# AD8403_SVF.net
KiCad netlist of a schematic drawn in EAGLE
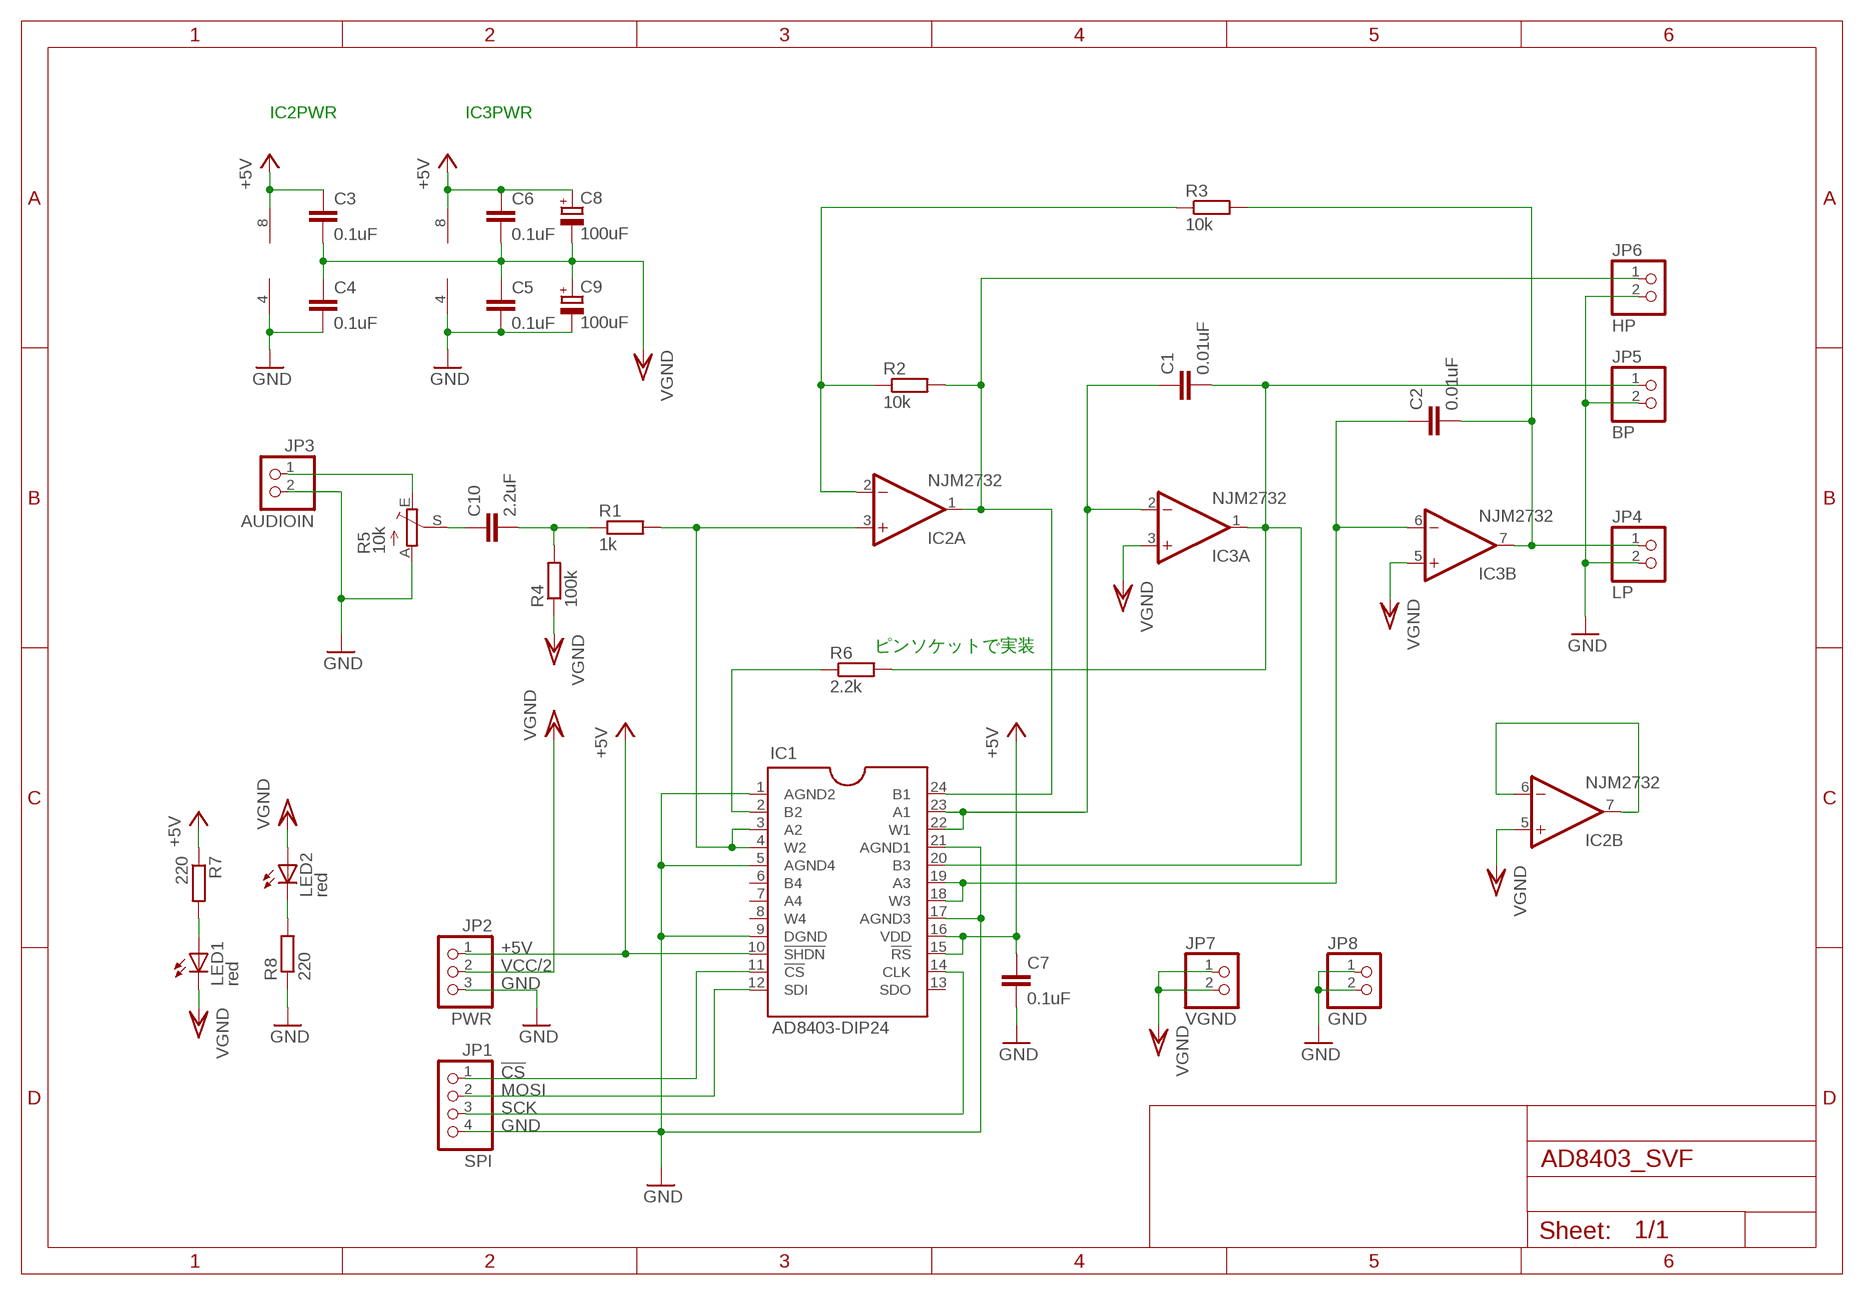
[diagram p0: schematic, sheet 1]

(export (version "E")
  (design (tool "Eeschema 10.0.6"))
  (components
    (comp (ref "C1")
      (value "0.01uF")
      (footprint "eagle-import:C050-025X075")
      (libsource (lib "eagle-import") (part "C-EU050-025X075"))
    )
    (comp (ref "C2")
      (value "0.01uF")
      (footprint "eagle-import:C050-025X075")
      (libsource (lib "eagle-import") (part "C-EU050-025X075"))
    )
    (comp (ref "C3")
      (value "0.1uF")
      (footprint "eagle-import:C025-024X044")
      (libsource (lib "eagle-import") (part "C-EU025-024X044"))
    )
    (comp (ref "C4")
      (value "0.1uF")
      (footprint "eagle-import:C025-024X044")
      (libsource (lib "eagle-import") (part "C-EU025-024X044"))
    )
    (comp (ref "C5")
      (value "0.1uF")
      (footprint "eagle-import:C025-024X044")
      (libsource (lib "eagle-import") (part "C-EU025-024X044"))
    )
    (comp (ref "C6")
      (value "0.1uF")
      (footprint "eagle-import:C025-024X044")
      (libsource (lib "eagle-import") (part "C-EU025-024X044"))
    )
    (comp (ref "C7")
      (value "0.1uF")
      (footprint "eagle-import:C025-024X044")
      (libsource (lib "eagle-import") (part "C-EU025-024X044"))
    )
    (comp (ref "C8")
      (value "100uF")
      (footprint "eagle-import:E2,5-7")
      (libsource (lib "eagle-import") (part "CPOL-EUE2.5-7"))
    )
    (comp (ref "C9")
      (value "100uF")
      (footprint "eagle-import:E2,5-7")
      (libsource (lib "eagle-import") (part "CPOL-EUE2.5-7"))
    )
    (comp (ref "C10")
      (value "2.2uF")
      (footprint "eagle-import:C050-055X075")
      (libsource (lib "eagle-import") (part "C-EU050-055X075"))
    )
    (comp (ref "IC1")
      (value "AD8403-DIP24")
      (footprint "eagle-import:AD8403_DIP24")
      (libsource (lib "eagle-import") (part "AD8403-DIP24"))
    )
    (comp (ref "IC2")
      (value "NJM2732")
      (footprint "eagle-import:DIL08")
      (libsource (lib "eagle-import") (part "4558NLM"))
    )
    (comp (ref "IC3")
      (value "NJM2732")
      (footprint "eagle-import:DIL08")
      (libsource (lib "eagle-import") (part "4558NLM"))
    )
    (comp (ref "JP1")
      (value "SPI")
      (footprint "eagle-import:1X04")
      (libsource (lib "eagle-import") (part "PINHD-1X4"))
    )
    (comp (ref "JP2")
      (value "PWR")
      (footprint "eagle-import:1X03")
      (libsource (lib "eagle-import") (part "PINHD-1X3"))
    )
    (comp (ref "JP3")
      (value "AUDIOIN")
      (footprint "eagle-import:1X02")
      (libsource (lib "eagle-import") (part "PINHD-1X2"))
    )
    (comp (ref "JP4")
      (value "LP")
      (footprint "eagle-import:1X02")
      (libsource (lib "eagle-import") (part "PINHD-1X2"))
    )
    (comp (ref "JP5")
      (value "BP")
      (footprint "eagle-import:1X02")
      (libsource (lib "eagle-import") (part "PINHD-1X2"))
    )
    (comp (ref "JP6")
      (value "HP")
      (footprint "eagle-import:1X02")
      (libsource (lib "eagle-import") (part "PINHD-1X2"))
    )
    (comp (ref "JP7")
      (value "VGND")
      (footprint "eagle-import:1X02")
      (libsource (lib "eagle-import") (part "PINHD-1X2"))
    )
    (comp (ref "JP8")
      (value "GND")
      (footprint "eagle-import:1X02")
      (libsource (lib "eagle-import") (part "PINHD-1X2"))
    )
    (comp (ref "LED1")
      (value "red")
      (footprint "eagle-import:LED3MM")
      (libsource (lib "eagle-import") (part "LED3MM"))
    )
    (comp (ref "LED2")
      (value "red")
      (footprint "eagle-import:LED3MM")
      (libsource (lib "eagle-import") (part "LED3MM"))
    )
    (comp (ref "R1")
      (value "1k")
      (footprint "eagle-import:0207_7")
      (libsource (lib "eagle-import") (part "R-EU_0207/7"))
    )
    (comp (ref "R2")
      (value "10k")
      (footprint "eagle-import:0207_7")
      (libsource (lib "eagle-import") (part "R-EU_0207/7"))
    )
    (comp (ref "R3")
      (value "10k")
      (footprint "eagle-import:0207_7")
      (libsource (lib "eagle-import") (part "R-EU_0207/7"))
    )
    (comp (ref "R4")
      (value "100k")
      (footprint "eagle-import:0207_7")
      (libsource (lib "eagle-import") (part "R-EU_0207/7"))
    )
    (comp (ref "R5")
      (value "10k")
      (footprint "eagle-import:B25P")
      (libsource (lib "eagle-import") (part "TRIM_EU-B25P"))
    )
    (comp (ref "R6")
      (value "2.2k")
      (footprint "eagle-import:0207_7")
      (libsource (lib "eagle-import") (part "R-EU_0207/7"))
    )
    (comp (ref "R7")
      (value "220")
      (footprint "eagle-import:0204V")
      (libsource (lib "eagle-import") (part "R-EU_0204/2V"))
    )
    (comp (ref "R8")
      (value "220")
      (footprint "eagle-import:0204V")
      (libsource (lib "eagle-import") (part "R-EU_0204/2V"))
    )
  )
  (nets
    (net (code "1") (name "+5V") (class "Default")
      (node (ref "C3") (pin "1") (pinfunction "1_1") (pintype "passive"))
      (node (ref "C6") (pin "1") (pinfunction "1_1") (pintype "passive"))
      (node (ref "C7") (pin "1") (pinfunction "1_1") (pintype "passive"))
      (node (ref "C8") (pin "+") (pinfunction "+_+") (pintype "passive"))
      (node (ref "IC1") (pin "10") (pinfunction "~{SHDN}_10") (pintype "passive"))
      (node (ref "IC1") (pin "15") (pinfunction "~{RS}_15") (pintype "passive"))
      (node (ref "IC1") (pin "16") (pinfunction "VDD_16") (pintype "passive"))
      (node (ref "IC2") (pin "8") (pinfunction "V+_8") (pintype "power_in"))
      (node (ref "IC3") (pin "8") (pinfunction "V+_8") (pintype "power_in"))
      (node (ref "JP2") (pin "1") (pinfunction "1_1") (pintype "passive"))
      (node (ref "R7") (pin "1") (pinfunction "1_1") (pintype "passive"))
    )
    (net (code "2") (name "/MOSI") (class "Default")
      (node (ref "IC1") (pin "12") (pinfunction "SDI_12") (pintype "passive"))
      (node (ref "JP1") (pin "2") (pinfunction "2_2") (pintype "passive"))
    )
    (net (code "3") (name "/SCK") (class "Default")
      (node (ref "IC1") (pin "14") (pinfunction "CLK_14") (pintype "passive"))
      (node (ref "JP1") (pin "3") (pinfunction "3_3") (pintype "passive"))
    )
    (net (code "4") (name "/~{CS}") (class "Default")
      (node (ref "IC1") (pin "11") (pinfunction "~{CS}_11") (pintype "passive"))
      (node (ref "JP1") (pin "1") (pinfunction "1_1") (pintype "passive"))
    )
    (net (code "5") (name "GND") (class "Default")
      (node (ref "C4") (pin "2") (pinfunction "2_2") (pintype "passive"))
      (node (ref "C5") (pin "2") (pinfunction "2_2") (pintype "passive"))
      (node (ref "C7") (pin "2") (pinfunction "2_2") (pintype "passive"))
      (node (ref "C9") (pin "-") (pinfunction "-_-") (pintype "passive"))
      (node (ref "IC1") (pin "1") (pinfunction "AGND2_1") (pintype "passive"))
      (node (ref "IC1") (pin "17") (pinfunction "AGND3_17") (pintype "passive"))
      (node (ref "IC1") (pin "21") (pinfunction "AGND1_21") (pintype "passive"))
      (node (ref "IC1") (pin "5") (pinfunction "AGND4_5") (pintype "passive"))
      (node (ref "IC1") (pin "9") (pinfunction "DGND_9") (pintype "passive"))
      (node (ref "IC2") (pin "4") (pinfunction "V-_4") (pintype "power_in"))
      (node (ref "IC3") (pin "4") (pinfunction "V-_4") (pintype "power_in"))
      (node (ref "JP1") (pin "4") (pinfunction "4_4") (pintype "passive"))
      (node (ref "JP2") (pin "3") (pinfunction "3_3") (pintype "passive"))
      (node (ref "JP3") (pin "2") (pinfunction "2_2") (pintype "passive"))
      (node (ref "JP4") (pin "2") (pinfunction "2_2") (pintype "passive"))
      (node (ref "JP5") (pin "2") (pinfunction "2_2") (pintype "passive"))
      (node (ref "JP6") (pin "2") (pinfunction "2_2") (pintype "passive"))
      (node (ref "JP8") (pin "1") (pinfunction "1_1") (pintype "passive"))
      (node (ref "JP8") (pin "2") (pinfunction "2_2") (pintype "passive"))
      (node (ref "R5") (pin "A") (pinfunction "A_A") (pintype "passive"))
      (node (ref "R8") (pin "1") (pinfunction "1_1") (pintype "passive"))
    )
    (net (code "6") (name "Net-(C10-Pad1)") (class "Default")
      (node (ref "C10") (pin "1") (pinfunction "1_1") (pintype "passive"))
      (node (ref "R5") (pin "S") (pinfunction "S_S") (pintype "passive"))
    )
    (net (code "7") (name "Net-(C10-Pad2)") (class "Default")
      (node (ref "C10") (pin "2") (pinfunction "2_2") (pintype "passive"))
      (node (ref "R1") (pin "1") (pinfunction "1_1") (pintype "passive"))
      (node (ref "R4") (pin "2") (pinfunction "2_2") (pintype "passive"))
    )
    (net (code "8") (name "Net-(IC1-A1)") (class "Default")
      (node (ref "C1") (pin "1") (pinfunction "1_1") (pintype "passive"))
      (node (ref "IC1") (pin "22") (pinfunction "W1_22") (pintype "passive"))
      (node (ref "IC1") (pin "23") (pinfunction "A1_23") (pintype "passive"))
      (node (ref "IC3") (pin "2") (pinfunction "-IN_2") (pintype "input"))
    )
    (net (code "9") (name "Net-(IC1-A2)") (class "Default")
      (node (ref "IC1") (pin "3") (pinfunction "A2_3") (pintype "passive"))
      (node (ref "IC1") (pin "4") (pinfunction "W2_4") (pintype "passive"))
      (node (ref "IC2") (pin "3") (pinfunction "+IN_3") (pintype "input"))
      (node (ref "R1") (pin "2") (pinfunction "2_2") (pintype "passive"))
    )
    (net (code "10") (name "Net-(IC1-A3)") (class "Default")
      (node (ref "C2") (pin "1") (pinfunction "1_1") (pintype "passive"))
      (node (ref "IC1") (pin "18") (pinfunction "W3_18") (pintype "passive"))
      (node (ref "IC1") (pin "19") (pinfunction "A3_19") (pintype "passive"))
      (node (ref "IC3") (pin "6") (pinfunction "-IN_6") (pintype "input"))
    )
    (net (code "11") (name "Net-(IC1-B1)") (class "Default")
      (node (ref "IC1") (pin "24") (pinfunction "B1_24") (pintype "passive"))
      (node (ref "IC2") (pin "1") (pinfunction "OUT_1") (pintype "output"))
      (node (ref "JP6") (pin "1") (pinfunction "1_1") (pintype "passive"))
      (node (ref "R2") (pin "2") (pinfunction "2_2") (pintype "passive"))
    )
    (net (code "12") (name "Net-(IC1-B2)") (class "Default")
      (node (ref "IC1") (pin "2") (pinfunction "B2_2") (pintype "passive"))
      (node (ref "R6") (pin "1") (pinfunction "1_1") (pintype "passive"))
    )
    (net (code "13") (name "Net-(IC1-B3)") (class "Default")
      (node (ref "C1") (pin "2") (pinfunction "2_2") (pintype "passive"))
      (node (ref "IC1") (pin "20") (pinfunction "B3_20") (pintype "passive"))
      (node (ref "IC3") (pin "1") (pinfunction "OUT_1") (pintype "output"))
      (node (ref "JP5") (pin "1") (pinfunction "1_1") (pintype "passive"))
      (node (ref "R6") (pin "2") (pinfunction "2_2") (pintype "passive"))
    )
    (net (code "14") (name "Net-(IC2A--IN)") (class "Default")
      (node (ref "IC2") (pin "2") (pinfunction "-IN_2") (pintype "input"))
      (node (ref "R2") (pin "1") (pinfunction "1_1") (pintype "passive"))
      (node (ref "R3") (pin "1") (pinfunction "1_1") (pintype "passive"))
    )
    (net (code "15") (name "Net-(IC2B--IN)") (class "Default")
      (node (ref "IC2") (pin "6") (pinfunction "-IN_6") (pintype "input"))
      (node (ref "IC2") (pin "7") (pinfunction "OUT_7") (pintype "output"))
    )
    (net (code "16") (name "Net-(IC3B-OUT)") (class "Default")
      (node (ref "C2") (pin "2") (pinfunction "2_2") (pintype "passive"))
      (node (ref "IC3") (pin "7") (pinfunction "OUT_7") (pintype "output"))
      (node (ref "JP4") (pin "1") (pinfunction "1_1") (pintype "passive"))
      (node (ref "R3") (pin "2") (pinfunction "2_2") (pintype "passive"))
    )
    (net (code "17") (name "Net-(JP3-Pad1)") (class "Default")
      (node (ref "JP3") (pin "1") (pinfunction "1_1") (pintype "passive"))
      (node (ref "R5") (pin "E") (pinfunction "E_E") (pintype "passive"))
    )
    (net (code "18") (name "Net-(LED1-PadA)") (class "Default")
      (node (ref "LED1") (pin "A") (pinfunction "A_A") (pintype "passive"))
      (node (ref "R7") (pin "2") (pinfunction "2_2") (pintype "passive"))
    )
    (net (code "19") (name "Net-(LED2-C)") (class "Default")
      (node (ref "LED2") (pin "K") (pinfunction "C_K") (pintype "passive"))
      (node (ref "R8") (pin "2") (pinfunction "2_2") (pintype "passive"))
    )
    (net (code "20") (name "VGND") (class "Default")
      (node (ref "C3") (pin "2") (pinfunction "2_2") (pintype "passive"))
      (node (ref "C4") (pin "1") (pinfunction "1_1") (pintype "passive"))
      (node (ref "C5") (pin "1") (pinfunction "1_1") (pintype "passive"))
      (node (ref "C6") (pin "2") (pinfunction "2_2") (pintype "passive"))
      (node (ref "C8") (pin "-") (pinfunction "-_-") (pintype "passive"))
      (node (ref "C9") (pin "+") (pinfunction "+_+") (pintype "passive"))
      (node (ref "IC2") (pin "5") (pinfunction "+IN_5") (pintype "input"))
      (node (ref "IC3") (pin "3") (pinfunction "+IN_3") (pintype "input"))
      (node (ref "IC3") (pin "5") (pinfunction "+IN_5") (pintype "input"))
      (node (ref "JP2") (pin "2") (pinfunction "2_2") (pintype "passive"))
      (node (ref "JP7") (pin "1") (pinfunction "1_1") (pintype "passive"))
      (node (ref "JP7") (pin "2") (pinfunction "2_2") (pintype "passive"))
      (node (ref "LED1") (pin "K") (pinfunction "C_K") (pintype "passive"))
      (node (ref "LED2") (pin "A") (pinfunction "A_A") (pintype "passive"))
      (node (ref "R4") (pin "1") (pinfunction "1_1") (pintype "passive"))
    )
    (net (code "21") (name "unconnected-(IC1-A4-Pad7)") (class "Default")
      (node (ref "IC1") (pin "7") (pinfunction "A4_7") (pintype "passive"))
    )
    (net (code "22") (name "unconnected-(IC1-B4-Pad6)") (class "Default")
      (node (ref "IC1") (pin "6") (pinfunction "B4_6") (pintype "passive"))
    )
    (net (code "23") (name "unconnected-(IC1-SDO-Pad13)") (class "Default")
      (node (ref "IC1") (pin "13") (pinfunction "SDO_13") (pintype "passive"))
    )
    (net (code "24") (name "unconnected-(IC1-W4-Pad8)") (class "Default")
      (node (ref "IC1") (pin "8") (pinfunction "W4_8") (pintype "passive"))
    )
  )
)
